# Port_Headers.net
KiCad netlist of a schematic drawn in Altium Designer
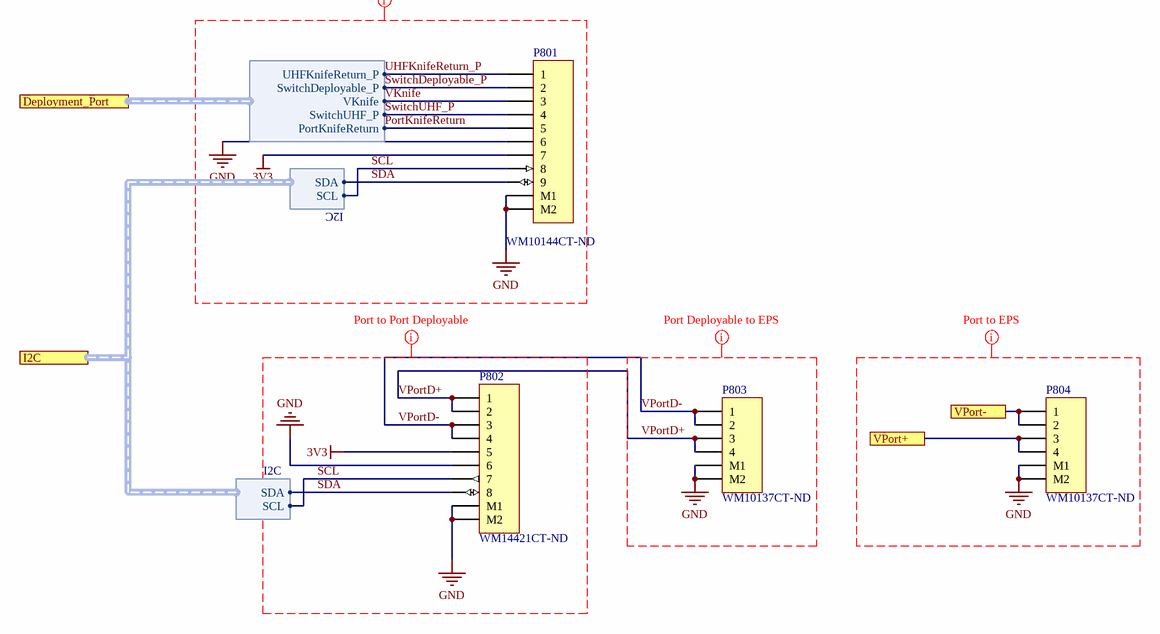
[diagram p0: Port_Headers.SchDoc]

(export (version "E")
  (design (tool "Eeschema 10.0.6"))
  (components
    (comp (ref "P801")
      (value "WM10144CT-ND")
      (footprint "MOLX-5040500991")
      (description "CONN HEADER SMD R/A 9POS 1.5MM")
      (fields
        (field (name "PART NUMBER") "68")
        (field (name "MANUFACTURER PART NUMBER") "5040500991")
        (field (name "PUBLISHER") "Altium Limited")
      )
      (libsource (lib "Database") (part "Header 11"))
    )
    (comp (ref "P802")
      (value "WM14421CT-ND")
      (footprint "MOLX-5040500891")
      (description "CONN HEADER SMD R/A 8POS 1.5MM")
      (fields
        (field (name "PART NUMBER") "67")
        (field (name "MANUFACTURER PART NUMBER") "5040500891")
        (field (name "PUBLISHER") "Altium Limited")
      )
      (libsource (lib "Database") (part "Header 10"))
    )
    (comp (ref "P803")
      (value "WM10137CT-ND")
      (footprint "MOLX-5040500491")
      (description "CONN HEADER SMD R/A 4POS 1.5MM")
      (fields
        (field (name "PART NUMBER") "63")
        (field (name "MANUFACTURER PART NUMBER") "5040500491")
        (field (name "PUBLISHER") "Altium Limited")
      )
      (libsource (lib "Database") (part "Header 6"))
    )
    (comp (ref "P804")
      (value "WM10137CT-ND")
      (footprint "MOLX-5040500491")
      (description "CONN HEADER SMD R/A 4POS 1.5MM")
      (fields
        (field (name "PART NUMBER") "63")
        (field (name "MANUFACTURER PART NUMBER") "5040500491")
        (field (name "PUBLISHER") "Altium Limited")
      )
      (libsource (lib "Database") (part "Header 6"))
    )
  )
  (nets
    (net (code "3") (name "/PortKnifeReturn") (class "Default")
      (node (ref "P801") (pin "5") (pinfunction "5_5") (pintype "passive"))
    )
    (net (code "4") (name "/SCL") (class "Default")
      (node (ref "P801") (pin "8") (pinfunction "8_8") (pintype "input"))
      (node (ref "P802") (pin "7") (pinfunction "7_7") (pintype "output"))
    )
    (net (code "5") (name "/SDA") (class "Default")
      (node (ref "P801") (pin "9") (pinfunction "9_9") (pintype "bidirectional"))
      (node (ref "P802") (pin "8") (pinfunction "8_8") (pintype "bidirectional"))
    )
    (net (code "6") (name "/SwitchDeployable_P") (class "Default")
      (node (ref "P801") (pin "2") (pinfunction "2_2") (pintype "passive"))
    )
    (net (code "7") (name "/SwitchUHF_P") (class "Default")
      (node (ref "P801") (pin "4") (pinfunction "4_4") (pintype "passive"))
    )
    (net (code "8") (name "/UHFKnifeReturn_P") (class "Default")
      (node (ref "P801") (pin "1") (pinfunction "1_1") (pintype "passive"))
    )
    (net (code "9") (name "/VKnife") (class "Default")
      (node (ref "P801") (pin "3") (pinfunction "3_3") (pintype "passive"))
    )
    (net (code "10") (name "/VPort+") (class "Default")
      (node (ref "P804") (pin "3") (pinfunction "3_3") (pintype "passive"))
      (node (ref "P804") (pin "4") (pinfunction "4_4") (pintype "passive"))
    )
    (net (code "11") (name "/VPort-") (class "Default")
      (node (ref "P804") (pin "1") (pinfunction "1_1") (pintype "passive"))
      (node (ref "P804") (pin "2") (pinfunction "2_2") (pintype "passive"))
    )
    (net (code "12") (name "/VPortD+") (class "Default")
      (node (ref "P802") (pin "1") (pinfunction "1_1") (pintype "passive"))
      (node (ref "P802") (pin "2") (pinfunction "2_2") (pintype "passive"))
      (node (ref "P803") (pin "3") (pinfunction "3_3") (pintype "passive"))
      (node (ref "P803") (pin "4") (pinfunction "4_4") (pintype "passive"))
    )
    (net (code "13") (name "/VPortD-") (class "Default")
      (node (ref "P802") (pin "3") (pinfunction "3_3") (pintype "passive"))
      (node (ref "P802") (pin "4") (pinfunction "4_4") (pintype "passive"))
      (node (ref "P803") (pin "1") (pinfunction "1_1") (pintype "passive"))
      (node (ref "P803") (pin "2") (pinfunction "2_2") (pintype "passive"))
    )
    (net (code "16") (name "3V3") (class "Default")
      (node (ref "P801") (pin "7") (pinfunction "7_7") (pintype "passive"))
      (node (ref "P802") (pin "5") (pinfunction "5_5") (pintype "passive"))
    )
    (net (code "17") (name "GND") (class "Default")
      (node (ref "P801") (pin "6") (pinfunction "6_6") (pintype "passive"))
      (node (ref "P801") (pin "M1") (pinfunction "M1_M1") (pintype "passive"))
      (node (ref "P801") (pin "M2") (pinfunction "M2_M2") (pintype "passive"))
      (node (ref "P802") (pin "6") (pinfunction "6_6") (pintype "passive"))
      (node (ref "P802") (pin "M1") (pinfunction "M1_M1") (pintype "passive"))
      (node (ref "P802") (pin "M2") (pinfunction "M2_M2") (pintype "passive"))
      (node (ref "P803") (pin "M1") (pinfunction "M1_M1") (pintype "passive"))
      (node (ref "P803") (pin "M2") (pinfunction "M2_M2") (pintype "passive"))
      (node (ref "P804") (pin "M1") (pinfunction "M1_M1") (pintype "passive"))
      (node (ref "P804") (pin "M2") (pinfunction "M2_M2") (pintype "passive"))
    )
  )
)
